# ProPrj_4pin__2025-03-10.net
KiCad netlist of a schematic drawn in EasyEDA Pro
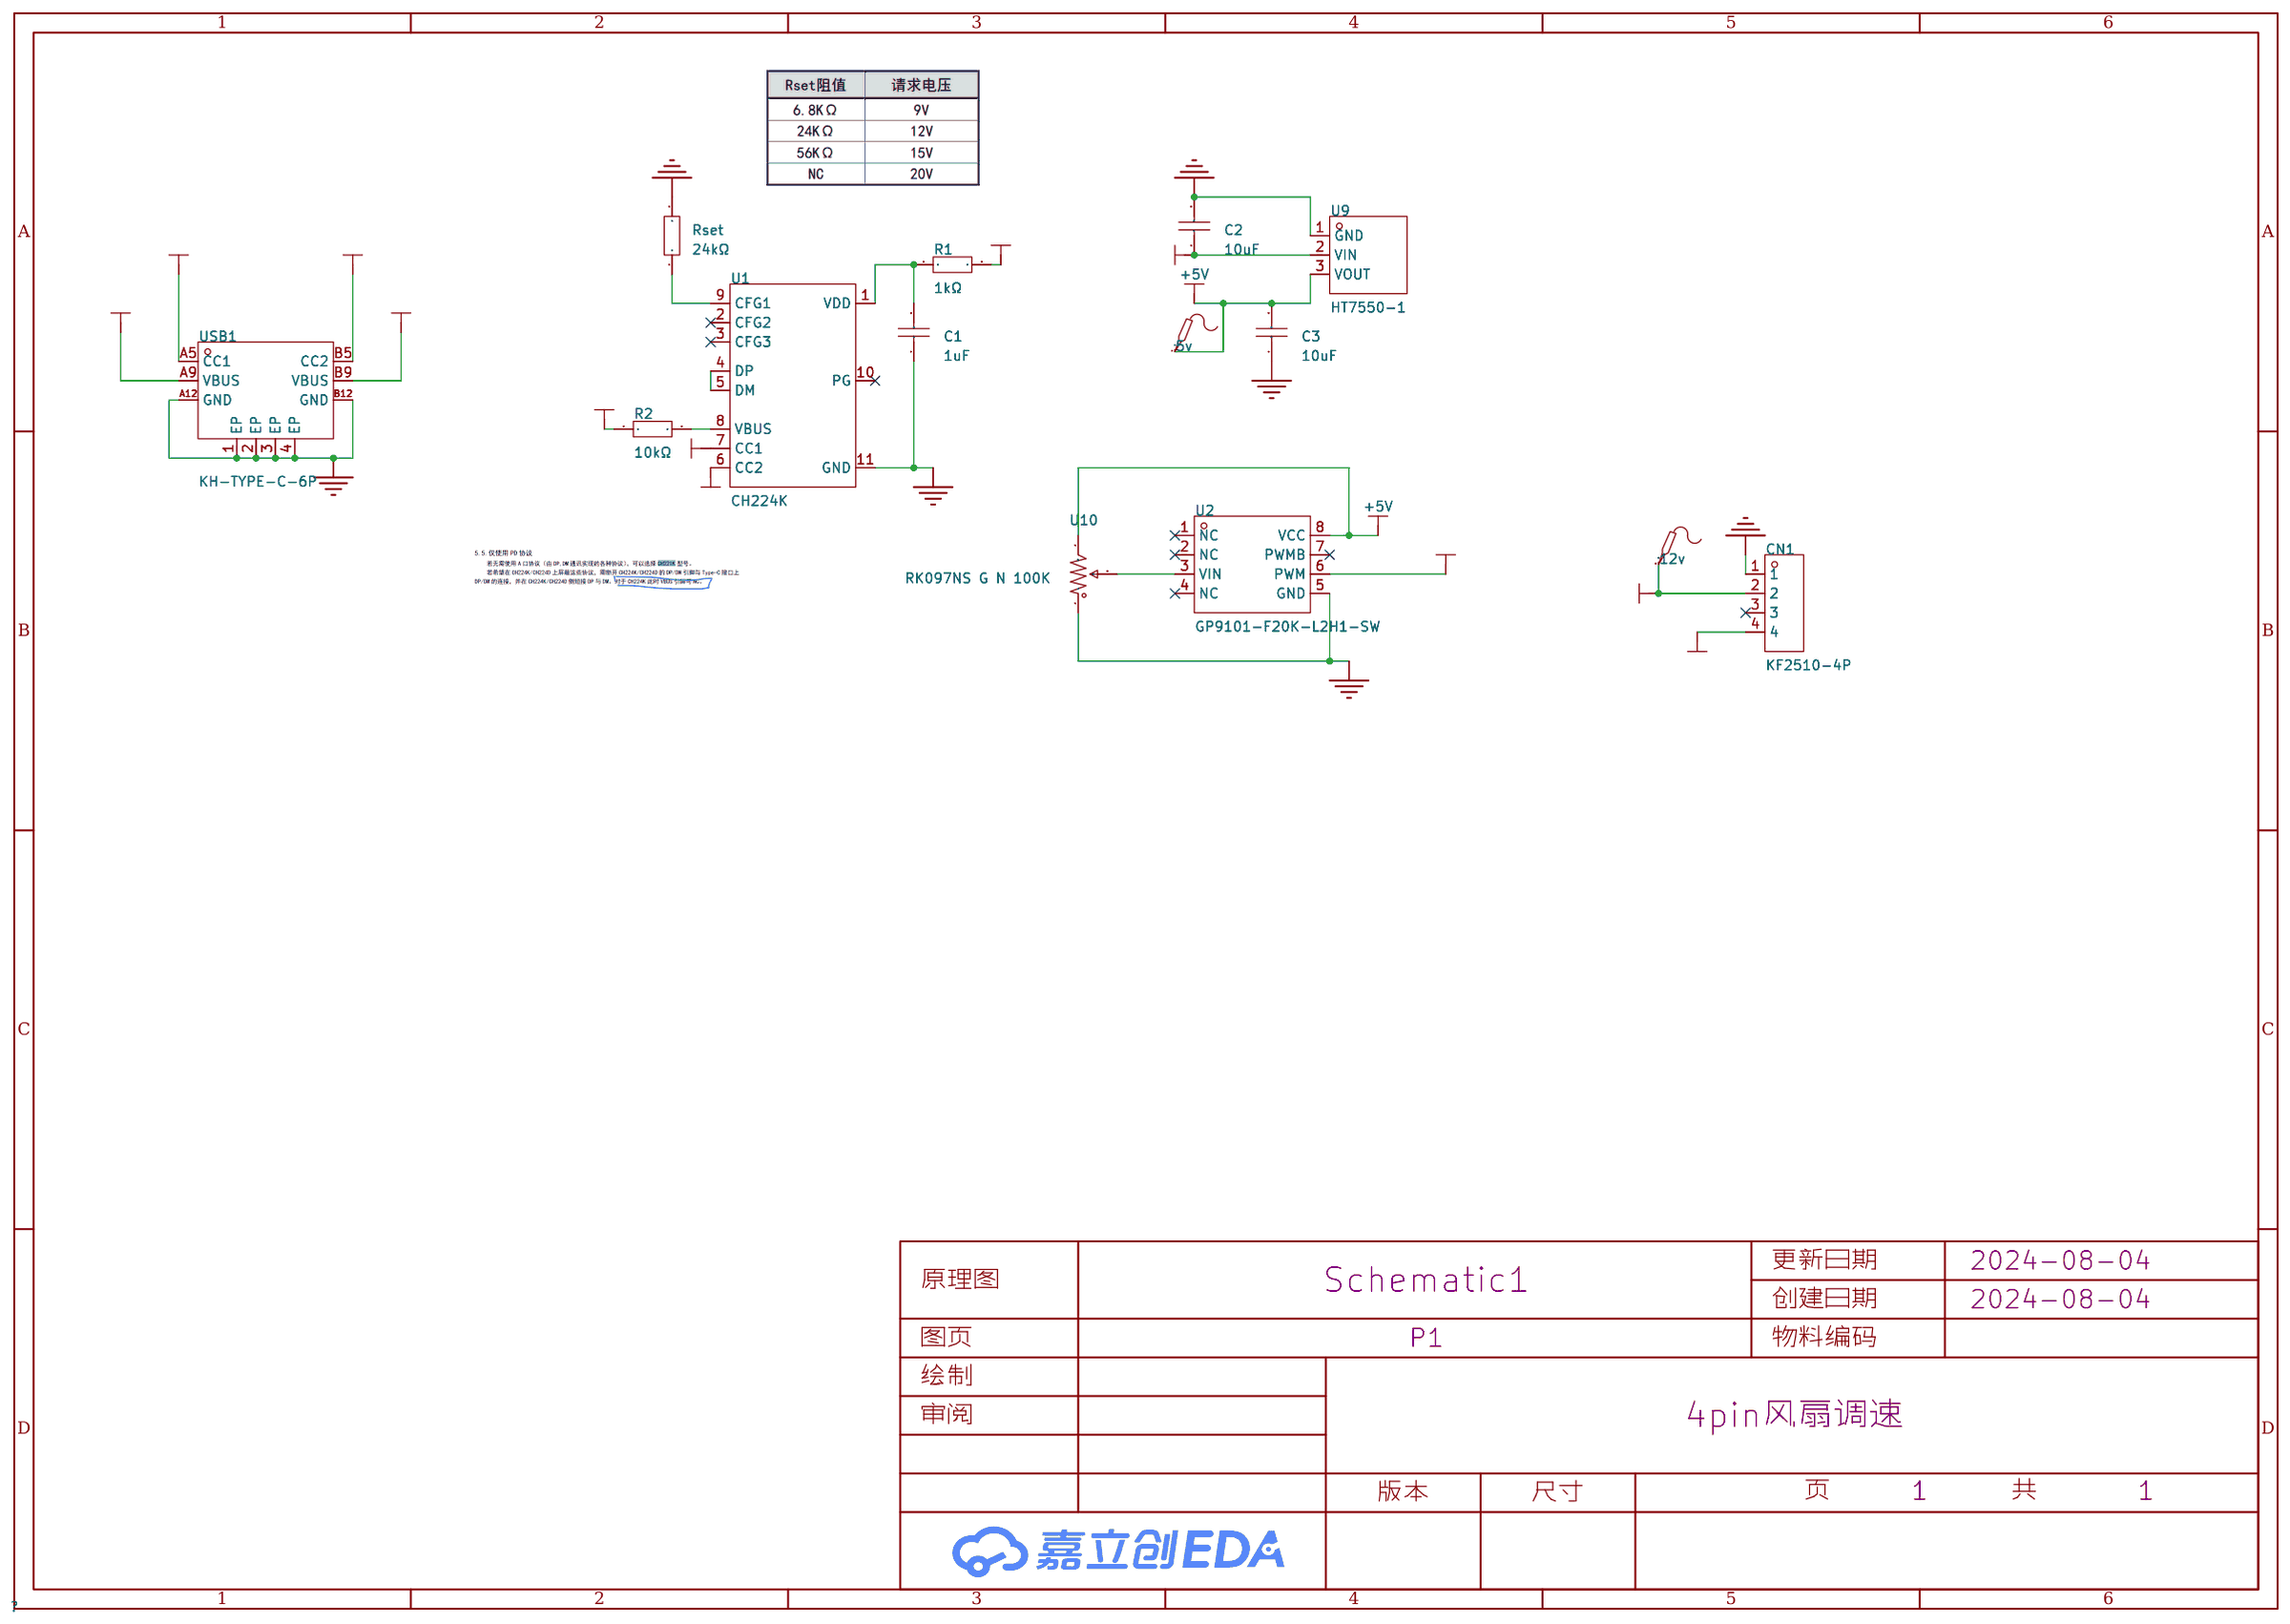
[diagram p0: schematic sheet]

(export (version "E")
  (design (tool "Eeschema 10.0.6"))
  (components
    (comp (ref "5v")
      (value "~")
      (footprint "easyedapro:Test-Point-0.5mm")
      (description "Test Point 测试点")
      (libsource (lib "easyedapro") (part "Test-Point"))
    )
    (comp (ref "12v")
      (value "~")
      (footprint "easyedapro:Test-Point-0.5mm")
      (description "Test Point 测试点")
      (libsource (lib "easyedapro") (part "Test-Point"))
    )
    (comp (ref "C1")
      (value "1uF")
      (footprint "easyedapro:C0805")
      (description "容值:20pF;精度:±5%;额定电压:50V;材质(温度系数):C0G;")
      (fields
        (field (name "Manufacturer Part") "CL21C200JBANNNC")
        (field (name "Manufacturer") "SAMSUNG(三星)")
      )
      (libsource (lib "easyedapro") (part "CL21C200JBANNNC"))
    )
    (comp (ref "C2")
      (value "10uF")
      (footprint "easyedapro:C0805")
      (description "容值:20pF;精度:±5%;额定电压:50V;材质(温度系数):C0G;")
      (fields
        (field (name "Manufacturer Part") "CL21C200JBANNNC")
        (field (name "Manufacturer") "SAMSUNG(三星)")
      )
      (libsource (lib "easyedapro") (part "CL21C200JBANNNC"))
    )
    (comp (ref "C3")
      (value "10uF")
      (footprint "easyedapro:C0805")
      (description "容值:20pF;精度:±5%;额定电压:50V;材质(温度系数):C0G;")
      (fields
        (field (name "Manufacturer Part") "CL21C200JBANNNC")
        (field (name "Manufacturer") "SAMSUNG(三星)")
      )
      (libsource (lib "easyedapro") (part "CL21C200JBANNNC"))
    )
    (comp (ref "CN1")
      (value "KF2510-4P")
      (footprint "easyedapro:CONN-TH_KF2510-4P")
      (libsource (lib "easyedapro") (part "KF2510-4P_C9900014236"))
    )
    (comp (ref "R1")
      (value "1kΩ")
      (footprint "easyedapro:R0805")
      (description "电阻类型:厚膜电阻;阻值:15kΩ;精度:±1%;功率:125mW;最大工作电压:150V;温度系数:±100ppm/°C;")
      (fields
        (field (name "Manufacturer Part") "0805W8F1502T5E")
        (field (name "Manufacturer") "UNI-ROYAL(厚声)")
      )
      (libsource (lib "easyedapro") (part "0805W8F1502T5E"))
    )
    (comp (ref "R2")
      (value "10kΩ")
      (footprint "easyedapro:R0805")
      (description "电阻类型:厚膜电阻;阻值:15kΩ;精度:±1%;功率:125mW;最大工作电压:150V;温度系数:±100ppm/°C;")
      (fields
        (field (name "Manufacturer Part") "0805W8F1502T5E")
        (field (name "Manufacturer") "UNI-ROYAL(厚声)")
      )
      (libsource (lib "easyedapro") (part "0805W8F1502T5E"))
    )
    (comp (ref "Rset")
      (value "24kΩ")
      (footprint "easyedapro:R0805")
      (description "电阻类型:厚膜电阻;阻值:15kΩ;精度:±1%;功率:125mW;最大工作电压:150V;温度系数:±100ppm/°C;")
      (fields
        (field (name "Manufacturer Part") "0805W8F1502T5E")
        (field (name "Manufacturer") "UNI-ROYAL(厚声)")
      )
      (libsource (lib "easyedapro") (part "0805W8F1502T5E"))
    )
    (comp (ref "U1")
      (value "CH224K")
      (footprint "easyedapro:ESSOP-10_L4.9-W3.9-P1.0-LS6.0-TL-EP")
      (description "应用功能:USB充电芯片;")
      (fields (field (name "Manufacturer") "WCH(南京沁恒)"))
      (libsource (lib "easyedapro") (part "CH224K"))
    )
    (comp (ref "U2")
      (value "GP9101-F20K-L2H1-SW")
      (footprint "easyedapro:SOP-8_L4.9-W3.9-P1.27-LS6.0-BL")
      (description "GP9101 0-VCC转PWM PWM频率 20KHz  输出特性 L2H1 ，占空比2%  拉低，占空比99% 拉高")
      (fields (field (name "Manufacturer") "Guestgood(客益)"))
      (libsource (lib "easyedapro") (part "GP9101-F20K-L2H1-SW_C3020260"))
    )
    (comp (ref "U9")
      (value "HT7550-1")
      (footprint "easyedapro:SOT-89_L4.5-W2.5-P1.50-LS4.2-BR")
      (fields (field (name "Manufacturer") "UMW(广东友台半导体)"))
      (libsource (lib "easyedapro") (part "HT7550-1_C347189"))
    )
    (comp (ref "U10")
      (value "RK097NS G N 100K")
      (footprint "easyedapro:RES-ADJ-TH_RK097111080J")
      (libsource (lib "easyedapro") (part "RK097NS G N"))
    )
    (comp (ref "USB1")
      (value "KH-TYPE-C-6P")
      (footprint "easyedapro:TYPE-C-SMD_TYPE-C-31-M-16")
      (description "连接器类型:Type-C;标准:-;公母:母;端口数量:1;触点数量:6P;安装方式:卧贴;额定电流 - 电源:5A;工作温度范围:-25°C~+85°C;")
      (fields (field (name "Manufacturer") "kinghelm(金航标)"))
      (libsource (lib "easyedapro") (part "KH-TYPE-C-6P_C2926725"))
    )
  )
  (nets
    (net (code "1") (name "+5V") (class "Default")
      (node (ref "5v") (pin "1") (pinfunction "1_1") (pintype "input"))
      (node (ref "C3") (pin "2") (pinfunction "2_2") (pintype "input"))
      (node (ref "U10") (pin "3") (pinfunction "3_3") (pintype "unspecified"))
      (node (ref "U2") (pin "8") (pinfunction "VCC_8") (pintype "unspecified"))
      (node (ref "U9") (pin "3") (pinfunction "VOUT_3") (pintype "input"))
    )
    (net (code "2") (name "CC1") (class "Default")
      (node (ref "U1") (pin "7") (pinfunction "CC1_7") (pintype "unspecified"))
      (node (ref "USB1") (pin "A5") (pinfunction "CC1_A5") (pintype "unspecified"))
    )
    (net (code "3") (name "CC2") (class "Default")
      (node (ref "U1") (pin "6") (pinfunction "CC2_6") (pintype "unspecified"))
      (node (ref "USB1") (pin "B5") (pinfunction "CC2_B5") (pintype "unspecified"))
    )
    (net (code "4") (name "GND") (class "Default")
      (node (ref "C1") (pin "1") (pinfunction "1_1") (pintype "input"))
      (node (ref "C2") (pin "2") (pinfunction "2_2") (pintype "input"))
      (node (ref "C3") (pin "1") (pinfunction "1_1") (pintype "input"))
      (node (ref "CN1") (pin "1") (pinfunction "1_1") (pintype "unspecified"))
      (node (ref "Rset") (pin "2") (pinfunction "2_2") (pintype "input"))
      (node (ref "U1") (pin "11") (pinfunction "GND_11") (pintype "unspecified"))
      (node (ref "U10") (pin "1") (pinfunction "1_1") (pintype "unspecified"))
      (node (ref "U2") (pin "5") (pinfunction "GND_5") (pintype "unspecified"))
      (node (ref "U9") (pin "1") (pinfunction "GND_1") (pintype "input"))
      (node (ref "USB1") (pin "1") (pinfunction "EP_1") (pintype "unspecified"))
      (node (ref "USB1") (pin "2") (pinfunction "EP_2") (pintype "unspecified"))
      (node (ref "USB1") (pin "3") (pinfunction "EP_3") (pintype "unspecified"))
      (node (ref "USB1") (pin "4") (pinfunction "EP_4") (pintype "unspecified"))
      (node (ref "USB1") (pin "A12") (pinfunction "GND_A12") (pintype "unspecified"))
      (node (ref "USB1") (pin "B12") (pinfunction "GND_B12") (pintype "unspecified"))
    )
    (net (code "5") (name "Net-(U1-CFG1)") (class "Default")
      (node (ref "Rset") (pin "1") (pinfunction "1_1") (pintype "input"))
      (node (ref "U1") (pin "9") (pinfunction "CFG1_9") (pintype "unspecified"))
    )
    (net (code "6") (name "Net-(U1-DM)") (class "Default")
      (node (ref "U1") (pin "4") (pinfunction "DP_4") (pintype "unspecified"))
      (node (ref "U1") (pin "5") (pinfunction "DM_5") (pintype "unspecified"))
    )
    (net (code "7") (name "Net-(U1-VBUS)") (class "Default")
      (node (ref "R2") (pin "2") (pinfunction "2_2") (pintype "input"))
      (node (ref "U1") (pin "8") (pinfunction "VBUS_8") (pintype "unspecified"))
    )
    (net (code "8") (name "Net-(U1-VDD)") (class "Default")
      (node (ref "C1") (pin "2") (pinfunction "2_2") (pintype "input"))
      (node (ref "R1") (pin "1") (pinfunction "1_1") (pintype "input"))
      (node (ref "U1") (pin "1") (pinfunction "VDD_1") (pintype "unspecified"))
    )
    (net (code "9") (name "Net-(U2-VIN)") (class "Default")
      (node (ref "U10") (pin "2") (pinfunction "2_2") (pintype "unspecified"))
      (node (ref "U2") (pin "3") (pinfunction "VIN_3") (pintype "unspecified"))
    )
    (net (code "10") (name "PWM") (class "Default")
      (node (ref "CN1") (pin "4") (pinfunction "4_4") (pintype "unspecified"))
      (node (ref "U2") (pin "6") (pinfunction "PWM_6") (pintype "unspecified"))
    )
    (net (code "11") (name "VBUS") (class "Default")
      (node (ref "12v") (pin "1") (pinfunction "1_1") (pintype "input"))
      (node (ref "C2") (pin "1") (pinfunction "1_1") (pintype "input"))
      (node (ref "CN1") (pin "2") (pinfunction "2_2") (pintype "unspecified"))
      (node (ref "R1") (pin "2") (pinfunction "2_2") (pintype "input"))
      (node (ref "R2") (pin "1") (pinfunction "1_1") (pintype "input"))
      (node (ref "U9") (pin "2") (pinfunction "VIN_2") (pintype "input"))
      (node (ref "USB1") (pin "A9") (pinfunction "VBUS_A9") (pintype "unspecified"))
      (node (ref "USB1") (pin "B9") (pinfunction "VBUS_B9") (pintype "unspecified"))
    )
    (net (code "12") (name "unconnected-(CN1-Pad3)") (class "Default")
      (node (ref "CN1") (pin "3") (pinfunction "3_3") (pintype "unspecified+no_connect"))
    )
    (net (code "13") (name "unconnected-(U1-CFG2-Pad2)") (class "Default")
      (node (ref "U1") (pin "2") (pinfunction "CFG2_2") (pintype "unspecified+no_connect"))
    )
    (net (code "14") (name "unconnected-(U1-CFG3-Pad3)") (class "Default")
      (node (ref "U1") (pin "3") (pinfunction "CFG3_3") (pintype "unspecified+no_connect"))
    )
    (net (code "15") (name "unconnected-(U1-PG-Pad10)") (class "Default")
      (node (ref "U1") (pin "10") (pinfunction "PG_10") (pintype "unspecified+no_connect"))
    )
    (net (code "16") (name "unconnected-(U2-NC-Pad1)") (class "Default")
      (node (ref "U2") (pin "1") (pinfunction "NC_1") (pintype "unspecified+no_connect"))
    )
    (net (code "17") (name "unconnected-(U2-NC-Pad2)") (class "Default")
      (node (ref "U2") (pin "2") (pinfunction "NC_2") (pintype "unspecified+no_connect"))
    )
    (net (code "18") (name "unconnected-(U2-NC-Pad4)") (class "Default")
      (node (ref "U2") (pin "4") (pinfunction "NC_4") (pintype "unspecified+no_connect"))
    )
    (net (code "19") (name "unconnected-(U2-PWMB-Pad7)") (class "Default")
      (node (ref "U2") (pin "7") (pinfunction "PWMB_7") (pintype "unspecified+no_connect"))
    )
  )
)
